# main_board.net
KiCad netlist of a schematic drawn in EAGLE
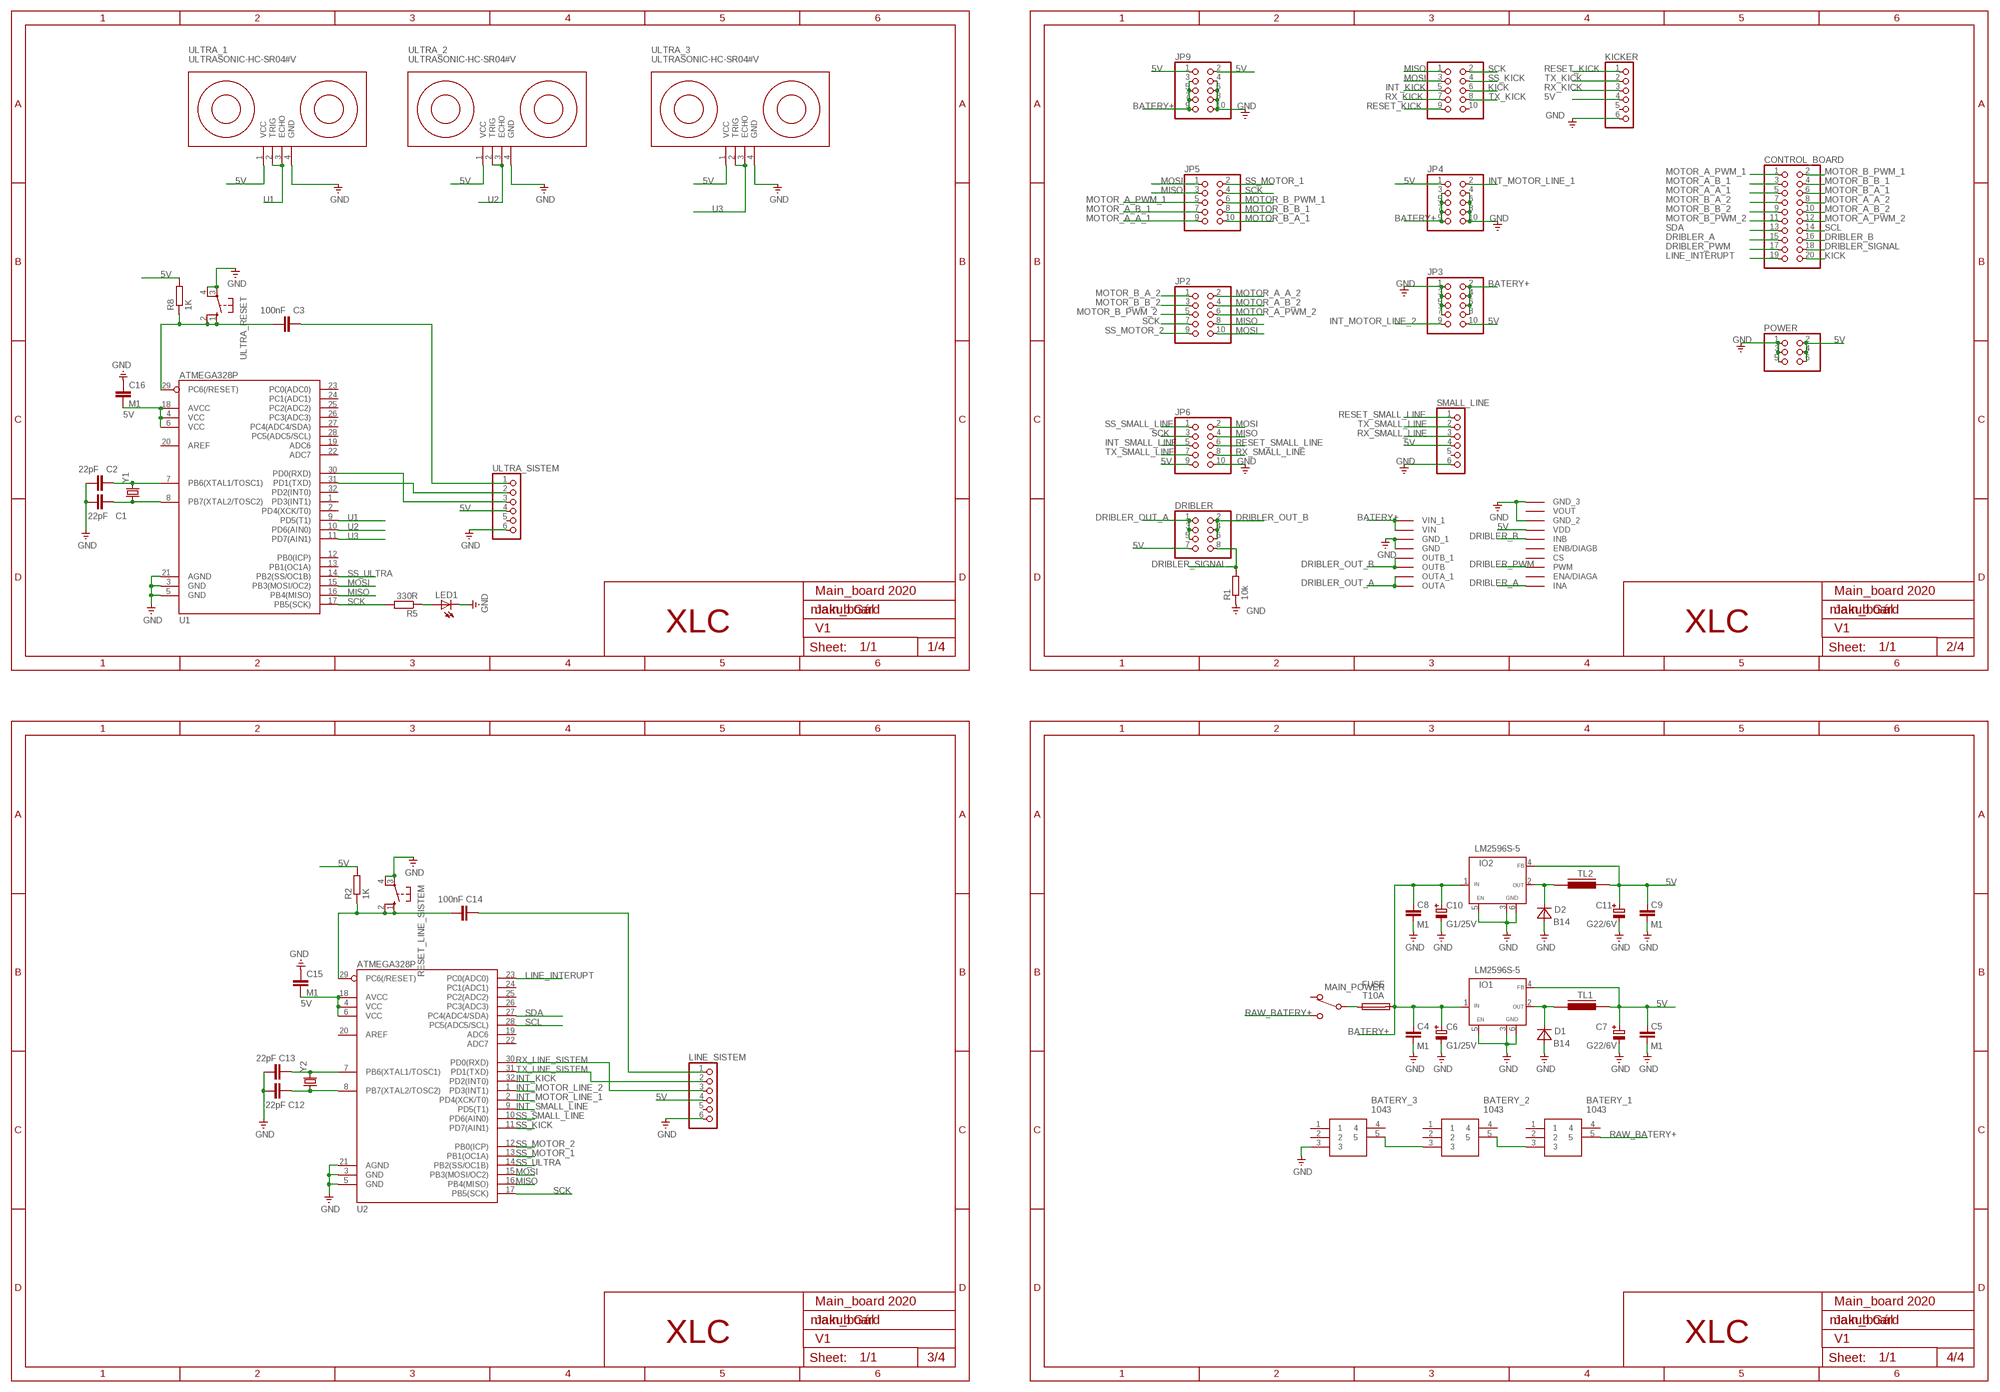
[diagram p0: schematic, sheet 1]

(export (version "E")
  (design (tool "Eeschema 10.0.6"))
  (components
    (comp (ref "BATERY_1")
      (value "1043")
      (footprint "eagle-import:1043")
      (fields (field (name "MOUSER_PART_NUMBER") "534-1043"))
      (libsource (lib "eagle-import") (part "1043"))
    )
    (comp (ref "BATERY_2")
      (value "1043")
      (footprint "eagle-import:1043")
      (fields (field (name "MOUSER_PART_NUMBER") "534-1043"))
      (libsource (lib "eagle-import") (part "1043"))
    )
    (comp (ref "BATERY_3")
      (value "1043")
      (footprint "eagle-import:1043")
      (fields (field (name "MOUSER_PART_NUMBER") "534-1043"))
      (libsource (lib "eagle-import") (part "1043"))
    )
    (comp (ref "C1")
      (value "22pF")
      (footprint "eagle-import:C0603")
      (libsource (lib "eagle-import") (part "C-EUC0603"))
    )
    (comp (ref "C2")
      (value "22pF")
      (footprint "eagle-import:C0603")
      (libsource (lib "eagle-import") (part "C-EUC0603"))
    )
    (comp (ref "C3")
      (value "100nF")
      (footprint "eagle-import:C0603")
      (libsource (lib "eagle-import") (part "C-EUC0603"))
    )
    (comp (ref "C4")
      (value "M1")
      (footprint "eagle-import:SMD-1206")
      (libsource (lib "eagle-import") (part "KOND-KERAM1206-SMD"))
    )
    (comp (ref "C5")
      (value "M1")
      (footprint "eagle-import:SMD-1206")
      (libsource (lib "eagle-import") (part "KOND-KERAM1206-SMD"))
    )
    (comp (ref "C6")
      (value "G1/25V")
      (footprint "eagle-import:SMD-ELE-D")
      (libsource (lib "eagle-import") (part "KOND-ELEKTD-SMD"))
    )
    (comp (ref "C7")
      (value "G22/6V")
      (footprint "eagle-import:SMD-ELE-D")
      (libsource (lib "eagle-import") (part "KOND-ELEKTD-SMD"))
    )
    (comp (ref "C8")
      (value "M1")
      (footprint "eagle-import:SMD-1206")
      (libsource (lib "eagle-import") (part "KOND-KERAM1206-SMD"))
    )
    (comp (ref "C9")
      (value "M1")
      (footprint "eagle-import:SMD-1206")
      (libsource (lib "eagle-import") (part "KOND-KERAM1206-SMD"))
    )
    (comp (ref "C10")
      (value "G1/25V")
      (footprint "eagle-import:SMD-ELE-D")
      (libsource (lib "eagle-import") (part "KOND-ELEKTD-SMD"))
    )
    (comp (ref "C11")
      (value "G22/6V")
      (footprint "eagle-import:SMD-ELE-D")
      (libsource (lib "eagle-import") (part "KOND-ELEKTD-SMD"))
    )
    (comp (ref "C12")
      (value "22pF")
      (footprint "eagle-import:C0603")
      (libsource (lib "eagle-import") (part "C-EUC0603"))
    )
    (comp (ref "C13")
      (value "22pF")
      (footprint "eagle-import:C0603")
      (libsource (lib "eagle-import") (part "C-EUC0603"))
    )
    (comp (ref "C14")
      (value "100nF")
      (footprint "eagle-import:C0603")
      (libsource (lib "eagle-import") (part "C-EUC0603"))
    )
    (comp (ref "C15")
      (value "M1")
      (footprint "eagle-import:C0603")
      (libsource (lib "eagle-import") (part "rcl_334_C-EUC0603"))
    )
    (comp (ref "C16")
      (value "M1")
      (footprint "eagle-import:C0603")
      (libsource (lib "eagle-import") (part "rcl_334_C-EUC0603"))
    )
    (comp (ref "CONTROL_BOARD")
      (value "PINHD-2X10_2.54-SMD")
      (footprint "eagle-import:2X10SMD")
      (libsource (lib "eagle-import") (part "PINHD-2X10_2.54-SMD"))
    )
    (comp (ref "D1")
      (value "B14")
      (footprint "eagle-import:D-3,6X5,5")
      (libsource (lib "eagle-import") (part "DIODASMD-3,6X5,5"))
    )
    (comp (ref "D2")
      (value "B14")
      (footprint "eagle-import:D-3,6X5,5")
      (libsource (lib "eagle-import") (part "DIODASMD-3,6X5,5"))
    )
    (comp (ref "DRIBLER")
      (value "PINHD-2X4_2.54-SMD")
      (footprint "eagle-import:2X04SMD")
      (libsource (lib "eagle-import") (part "PINHD-2X4_2.54-SMD"))
    )
    (comp (ref "FUSE")
      (value "T10A")
      (footprint "eagle-import:SH22,5A")
      (libsource (lib "eagle-import") (part "POISTKA2A"))
    )
    (comp (ref "IO1")
      (value "LM2596S-5")
      (footprint "eagle-import:TO263-5")
      (libsource (lib "eagle-import") (part "LM2596S"))
    )
    (comp (ref "IO2")
      (value "LM2596S-5")
      (footprint "eagle-import:TO263-5")
      (libsource (lib "eagle-import") (part "LM2596S"))
    )
    (comp (ref "JP2")
      (value "PINHD-2X5_2.54-SMD")
      (footprint "eagle-import:2X05SMD")
      (libsource (lib "eagle-import") (part "PINHD-2X5_2.54-SMD"))
    )
    (comp (ref "JP3")
      (value "PINHD-2X5_2.54-SMD")
      (footprint "eagle-import:2X05SMD")
      (libsource (lib "eagle-import") (part "PINHD-2X5_2.54-SMD"))
    )
    (comp (ref "JP4")
      (value "PINHD-2X5_2.54-SMD")
      (footprint "eagle-import:2X05SMD")
      (libsource (lib "eagle-import") (part "PINHD-2X5_2.54-SMD"))
    )
    (comp (ref "JP5")
      (value "PINHD-2X5_2.54-SMD")
      (footprint "eagle-import:2X05SMD")
      (libsource (lib "eagle-import") (part "PINHD-2X5_2.54-SMD"))
    )
    (comp (ref "JP6")
      (value "PINHD-2X5_2.54-SMD")
      (footprint "eagle-import:2X05SMD")
      (libsource (lib "eagle-import") (part "PINHD-2X5_2.54-SMD"))
    )
    (comp (ref "JP8")
      (value "PINHD-2X5_2.54-SMD")
      (footprint "eagle-import:2X05SMD")
      (libsource (lib "eagle-import") (part "PINHD-2X5_2.54-SMD"))
    )
    (comp (ref "JP9")
      (value "PINHD-2X5_2.54-SMD")
      (footprint "eagle-import:2X05SMD")
      (libsource (lib "eagle-import") (part "PINHD-2X5_2.54-SMD"))
    )
    (comp (ref "KICKER")
      (value "PINHD-1X6")
      (footprint "eagle-import:1X06")
      (libsource (lib "eagle-import") (part "PINHD-1X6"))
    )
    (comp (ref "LED1")
      (value "LEDCHIPLED_0603")
      (footprint "eagle-import:CHIPLED_0603")
      (libsource (lib "eagle-import") (part "LEDCHIPLED_0603"))
    )
    (comp (ref "LINE_SISTEM")
      (value "PINHD-1X6")
      (footprint "eagle-import:1X06")
      (libsource (lib "eagle-import") (part "PINHD-1X6"))
    )
    (comp (ref "MAIN_POWER")
      (value "PREP-1PB")
      (footprint "eagle-import:P-B069B")
      (libsource (lib "eagle-import") (part "PREP-1PB"))
    )
    (comp (ref "POWER")
      (value "PINHD-2X3_2.54-SMD")
      (footprint "eagle-import:2X03SMD")
      (libsource (lib "eagle-import") (part "PINHD-2X3_2.54-SMD"))
    )
    (comp (ref "R1")
      (value "10k")
      (footprint "eagle-import:R0603")
      (libsource (lib "eagle-import") (part "R-EU_R0603"))
    )
    (comp (ref "R2")
      (value "1K")
      (footprint "eagle-import:R0603")
      (libsource (lib "eagle-import") (part "R-EU_R0603"))
    )
    (comp (ref "R5")
      (value "330R")
      (footprint "eagle-import:R0603")
      (libsource (lib "eagle-import") (part "R-EU_R0603"))
    )
    (comp (ref "R8")
      (value "1K")
      (footprint "eagle-import:R0603")
      (libsource (lib "eagle-import") (part "R-EU_R0603"))
    )
    (comp (ref "RESET_LINE_SISTEM")
      (value "10-XX")
      (footprint "eagle-import:B3F-10XX")
      (fields (field (name "MPN") "B3F-1000"))
      (libsource (lib "eagle-import") (part "10-XX"))
    )
    (comp (ref "SMALL_LINE")
      (value "PINHD-1X6")
      (footprint "eagle-import:1X06")
      (libsource (lib "eagle-import") (part "PINHD-1X6"))
    )
    (comp (ref "TL1")
      (value "INDUK-TLSMD1")
      (footprint "eagle-import:INDUK-TL")
      (libsource (lib "eagle-import") (part "INDUK-TLSMD1"))
    )
    (comp (ref "TL2")
      (value "INDUK-TLSMD1")
      (footprint "eagle-import:INDUK-TL")
      (libsource (lib "eagle-import") (part "INDUK-TLSMD1"))
    )
    (comp (ref "U$4")
      (value "MOTOR_DRIVER")
      (footprint "eagle-import:MOTOR_DRIVER")
      (libsource (lib "eagle-import") (part "MOTOR_DRIVER"))
    )
    (comp (ref "U1")
      (value "ATMEGA328P")
      (footprint "eagle-import:TQFP32-08")
      (libsource (lib "eagle-import") (part "ATMEGA328_SMT"))
    )
    (comp (ref "U2")
      (value "ATMEGA328P")
      (footprint "eagle-import:TQFP32-08")
      (libsource (lib "eagle-import") (part "ATMEGA328_SMT"))
    )
    (comp (ref "ULTRA_1")
      (value "ULTRASONIC-HC-SR04#V")
      (footprint "eagle-import:ULTRASONIC-HC-SR04#V")
      (libsource (lib "eagle-import") (part "ULTRASONIC-HC-SR04#V"))
    )
    (comp (ref "ULTRA_2")
      (value "ULTRASONIC-HC-SR04#V")
      (footprint "eagle-import:ULTRASONIC-HC-SR04#V")
      (libsource (lib "eagle-import") (part "ULTRASONIC-HC-SR04#V"))
    )
    (comp (ref "ULTRA_3")
      (value "ULTRASONIC-HC-SR04#V")
      (footprint "eagle-import:ULTRASONIC-HC-SR04#V")
      (libsource (lib "eagle-import") (part "ULTRASONIC-HC-SR04#V"))
    )
    (comp (ref "ULTRA_RESET")
      (value "10-XX")
      (footprint "eagle-import:B3F-10XX")
      (fields (field (name "MPN") "B3F-1000"))
      (libsource (lib "eagle-import") (part "10-XX"))
    )
    (comp (ref "ULTRA_SISTEM")
      (value "PINHD-1X6")
      (footprint "eagle-import:1X06")
      (libsource (lib "eagle-import") (part "PINHD-1X6"))
    )
    (comp (ref "Y1")
      (value "CRYSTALHC49US")
      (footprint "eagle-import:HC49US")
      (libsource (lib "eagle-import") (part "CRYSTALHC49US"))
    )
    (comp (ref "Y2")
      (value "CRYSTALHC49US")
      (footprint "eagle-import:HC49US")
      (libsource (lib "eagle-import") (part "CRYSTALHC49US"))
    )
  )
  (nets
    (net (code "1") (name "/5V") (class "Default")
      (node (ref "C11") (pin "PLUS") (pinfunction "PLUS_PLUS") (pintype "passive"))
      (node (ref "C15") (pin "2") (pinfunction "2_2") (pintype "passive"))
      (node (ref "C16") (pin "2") (pinfunction "2_2") (pintype "passive"))
      (node (ref "C5") (pin "2") (pinfunction "2_2") (pintype "passive"))
      (node (ref "C7") (pin "PLUS") (pinfunction "PLUS_PLUS") (pintype "passive"))
      (node (ref "C9") (pin "2") (pinfunction "2_2") (pintype "passive"))
      (node (ref "DRIBLER") (pin "7") (pinfunction "7_7") (pintype "passive"))
      (node (ref "IO1") (pin "4") (pinfunction "FB_4") (pintype "input"))
      (node (ref "IO2") (pin "4") (pinfunction "FB_4") (pintype "input"))
      (node (ref "JP3") (pin "10") (pinfunction "10_10") (pintype "passive"))
      (node (ref "JP4") (pin "1") (pinfunction "1_1") (pintype "passive"))
      (node (ref "JP6") (pin "9") (pinfunction "9_9") (pintype "passive"))
      (node (ref "JP9") (pin "1") (pinfunction "1_1") (pintype "passive"))
      (node (ref "JP9") (pin "2") (pinfunction "2_2") (pintype "passive"))
      (node (ref "KICKER") (pin "4") (pinfunction "4_4") (pintype "passive"))
      (node (ref "LINE_SISTEM") (pin "4") (pinfunction "4_4") (pintype "passive"))
      (node (ref "POWER") (pin "2") (pinfunction "2_2") (pintype "passive"))
      (node (ref "POWER") (pin "4") (pinfunction "4_4") (pintype "passive"))
      (node (ref "POWER") (pin "6") (pinfunction "6_6") (pintype "passive"))
      (node (ref "R2") (pin "2") (pinfunction "2_2") (pintype "passive"))
      (node (ref "R8") (pin "2") (pinfunction "2_2") (pintype "passive"))
      (node (ref "SMALL_LINE") (pin "4") (pinfunction "4_4") (pintype "passive"))
      (node (ref "TL1") (pin "2") (pinfunction "2_2") (pintype "passive"))
      (node (ref "TL2") (pin "2") (pinfunction "2_2") (pintype "passive"))
      (node (ref "U$4") (pin "VDD") (pinfunction "VDD_VDD") (pintype "bidirectional"))
      (node (ref "U1") (pin "18") (pinfunction "AVCC_18") (pintype "bidirectional"))
      (node (ref "U1") (pin "4") (pinfunction "VCC_4") (pintype "bidirectional"))
      (node (ref "U1") (pin "6") (pinfunction "VCC_6") (pintype "bidirectional"))
      (node (ref "U2") (pin "18") (pinfunction "AVCC_18") (pintype "bidirectional"))
      (node (ref "U2") (pin "4") (pinfunction "VCC_4") (pintype "bidirectional"))
      (node (ref "U2") (pin "6") (pinfunction "VCC_6") (pintype "bidirectional"))
      (node (ref "ULTRA_1") (pin "1") (pinfunction "VCC_1") (pintype "power_in"))
      (node (ref "ULTRA_2") (pin "1") (pinfunction "VCC_1") (pintype "power_in"))
      (node (ref "ULTRA_3") (pin "1") (pinfunction "VCC_1") (pintype "power_in"))
      (node (ref "ULTRA_SISTEM") (pin "4") (pinfunction "4_4") (pintype "passive"))
    )
    (net (code "2") (name "/BATERY+") (class "Default")
      (node (ref "C10") (pin "PLUS") (pinfunction "PLUS_PLUS") (pintype "passive"))
      (node (ref "C4") (pin "2") (pinfunction "2_2") (pintype "passive"))
      (node (ref "C6") (pin "PLUS") (pinfunction "PLUS_PLUS") (pintype "passive"))
      (node (ref "C8") (pin "2") (pinfunction "2_2") (pintype "passive"))
      (node (ref "FUSE") (pin "2") (pinfunction "2_2") (pintype "passive"))
      (node (ref "IO1") (pin "1") (pinfunction "IN_1") (pintype "input"))
      (node (ref "IO2") (pin "1") (pinfunction "IN_1") (pintype "input"))
      (node (ref "JP3") (pin "2") (pinfunction "2_2") (pintype "passive"))
      (node (ref "JP3") (pin "4") (pinfunction "4_4") (pintype "passive"))
      (node (ref "JP3") (pin "6") (pinfunction "6_6") (pintype "passive"))
      (node (ref "JP3") (pin "8") (pinfunction "8_8") (pintype "passive"))
      (node (ref "JP4") (pin "3") (pinfunction "3_3") (pintype "passive"))
      (node (ref "JP4") (pin "5") (pinfunction "5_5") (pintype "passive"))
      (node (ref "JP4") (pin "7") (pinfunction "7_7") (pintype "passive"))
      (node (ref "JP4") (pin "9") (pinfunction "9_9") (pintype "passive"))
      (node (ref "JP9") (pin "3") (pinfunction "3_3") (pintype "passive"))
      (node (ref "JP9") (pin "5") (pinfunction "5_5") (pintype "passive"))
      (node (ref "JP9") (pin "7") (pinfunction "7_7") (pintype "passive"))
      (node (ref "JP9") (pin "9") (pinfunction "9_9") (pintype "passive"))
      (node (ref "U$4") (pin "VIN") (pinfunction "VIN_VIN") (pintype "bidirectional"))
      (node (ref "U$4") (pin "VIN_1") (pinfunction "VIN_1_VIN_1") (pintype "bidirectional"))
    )
    (net (code "3") (name "/DRIBLER_A") (class "Default")
      (node (ref "CONTROL_BOARD") (pin "15") (pinfunction "15_15") (pintype "passive"))
      (node (ref "U$4") (pin "INA") (pinfunction "INA_INA") (pintype "bidirectional"))
    )
    (net (code "4") (name "/DRIBLER_B") (class "Default")
      (node (ref "CONTROL_BOARD") (pin "16") (pinfunction "16_16") (pintype "passive"))
      (node (ref "U$4") (pin "INB") (pinfunction "INB_INB") (pintype "bidirectional"))
    )
    (net (code "5") (name "/DRIBLER_OUT_A") (class "Default")
      (node (ref "DRIBLER") (pin "1") (pinfunction "1_1") (pintype "passive"))
      (node (ref "DRIBLER") (pin "3") (pinfunction "3_3") (pintype "passive"))
      (node (ref "DRIBLER") (pin "5") (pinfunction "5_5") (pintype "passive"))
      (node (ref "U$4") (pin "OUTA") (pinfunction "OUTA_OUTA") (pintype "bidirectional"))
      (node (ref "U$4") (pin "OUTA_1") (pinfunction "OUTA_1_OUTA_1") (pintype "bidirectional"))
    )
    (net (code "6") (name "/DRIBLER_OUT_B") (class "Default")
      (node (ref "DRIBLER") (pin "2") (pinfunction "2_2") (pintype "passive"))
      (node (ref "DRIBLER") (pin "4") (pinfunction "4_4") (pintype "passive"))
      (node (ref "DRIBLER") (pin "6") (pinfunction "6_6") (pintype "passive"))
      (node (ref "U$4") (pin "OUTB") (pinfunction "OUTB_OUTB") (pintype "bidirectional"))
      (node (ref "U$4") (pin "OUTB_1") (pinfunction "OUTB_1_OUTB_1") (pintype "bidirectional"))
    )
    (net (code "7") (name "/DRIBLER_PWM") (class "Default")
      (node (ref "CONTROL_BOARD") (pin "17") (pinfunction "17_17") (pintype "passive"))
      (node (ref "U$4") (pin "PWM") (pinfunction "PWM_PWM") (pintype "bidirectional"))
    )
    (net (code "8") (name "/DRIBLER_SIGNAL") (class "Default")
      (node (ref "CONTROL_BOARD") (pin "18") (pinfunction "18_18") (pintype "passive"))
      (node (ref "DRIBLER") (pin "8") (pinfunction "8_8") (pintype "passive"))
      (node (ref "R1") (pin "2") (pinfunction "2_2") (pintype "passive"))
    )
    (net (code "9") (name "/INT_KICK") (class "Default")
      (node (ref "JP8") (pin "5") (pinfunction "5_5") (pintype "passive"))
      (node (ref "U2") (pin "32") (pinfunction "PD2(INT0)_32") (pintype "bidirectional"))
    )
    (net (code "10") (name "/INT_MOTOR_LINE_1") (class "Default")
      (node (ref "JP4") (pin "2") (pinfunction "2_2") (pintype "passive"))
      (node (ref "U2") (pin "2") (pinfunction "PD4(XCK/T0)_2") (pintype "bidirectional"))
    )
    (net (code "11") (name "/INT_MOTOR_LINE_2") (class "Default")
      (node (ref "JP3") (pin "9") (pinfunction "9_9") (pintype "passive"))
      (node (ref "U2") (pin "1") (pinfunction "PD3(INT1)_1") (pintype "bidirectional"))
    )
    (net (code "12") (name "/INT_SMALL_LINE") (class "Default")
      (node (ref "JP6") (pin "5") (pinfunction "5_5") (pintype "passive"))
      (node (ref "U2") (pin "9") (pinfunction "PD5(T1)_9") (pintype "bidirectional"))
    )
    (net (code "13") (name "/KICK") (class "Default")
      (node (ref "CONTROL_BOARD") (pin "20") (pinfunction "20_20") (pintype "passive"))
      (node (ref "JP8") (pin "6") (pinfunction "6_6") (pintype "passive"))
    )
    (net (code "14") (name "/LINE_INTERUPT") (class "Default")
      (node (ref "CONTROL_BOARD") (pin "19") (pinfunction "19_19") (pintype "passive"))
      (node (ref "U2") (pin "23") (pinfunction "PC0(ADC0)_23") (pintype "bidirectional"))
    )
    (net (code "15") (name "/MISO") (class "Default")
      (node (ref "JP2") (pin "8") (pinfunction "8_8") (pintype "passive"))
      (node (ref "JP5") (pin "3") (pinfunction "3_3") (pintype "passive"))
      (node (ref "JP6") (pin "4") (pinfunction "4_4") (pintype "passive"))
      (node (ref "JP8") (pin "1") (pinfunction "1_1") (pintype "passive"))
      (node (ref "U1") (pin "16") (pinfunction "PB4(MISO)_16") (pintype "bidirectional"))
      (node (ref "U2") (pin "16") (pinfunction "PB4(MISO)_16") (pintype "bidirectional"))
    )
    (net (code "16") (name "/MOSI") (class "Default")
      (node (ref "JP2") (pin "10") (pinfunction "10_10") (pintype "passive"))
      (node (ref "JP5") (pin "1") (pinfunction "1_1") (pintype "passive"))
      (node (ref "JP6") (pin "2") (pinfunction "2_2") (pintype "passive"))
      (node (ref "JP8") (pin "3") (pinfunction "3_3") (pintype "passive"))
      (node (ref "U1") (pin "15") (pinfunction "PB3(MOSI/OC2)_15") (pintype "bidirectional"))
      (node (ref "U2") (pin "15") (pinfunction "PB3(MOSI/OC2)_15") (pintype "bidirectional"))
    )
    (net (code "17") (name "/MOTOR_A_A_1") (class "Default")
      (node (ref "CONTROL_BOARD") (pin "5") (pinfunction "5_5") (pintype "passive"))
      (node (ref "JP5") (pin "9") (pinfunction "9_9") (pintype "passive"))
    )
    (net (code "18") (name "/MOTOR_A_A_2") (class "Default")
      (node (ref "CONTROL_BOARD") (pin "8") (pinfunction "8_8") (pintype "passive"))
      (node (ref "JP2") (pin "2") (pinfunction "2_2") (pintype "passive"))
    )
    (net (code "19") (name "/MOTOR_A_B_1") (class "Default")
      (node (ref "CONTROL_BOARD") (pin "3") (pinfunction "3_3") (pintype "passive"))
      (node (ref "JP5") (pin "7") (pinfunction "7_7") (pintype "passive"))
    )
    (net (code "20") (name "/MOTOR_A_B_2") (class "Default")
      (node (ref "CONTROL_BOARD") (pin "10") (pinfunction "10_10") (pintype "passive"))
      (node (ref "JP2") (pin "4") (pinfunction "4_4") (pintype "passive"))
    )
    (net (code "21") (name "/MOTOR_A_PWM_1") (class "Default")
      (node (ref "CONTROL_BOARD") (pin "1") (pinfunction "1_1") (pintype "passive"))
      (node (ref "JP5") (pin "5") (pinfunction "5_5") (pintype "passive"))
    )
    (net (code "22") (name "/MOTOR_A_PWM_2") (class "Default")
      (node (ref "CONTROL_BOARD") (pin "12") (pinfunction "12_12") (pintype "passive"))
      (node (ref "JP2") (pin "6") (pinfunction "6_6") (pintype "passive"))
    )
    (net (code "23") (name "/MOTOR_B_A_1") (class "Default")
      (node (ref "CONTROL_BOARD") (pin "6") (pinfunction "6_6") (pintype "passive"))
      (node (ref "JP5") (pin "10") (pinfunction "10_10") (pintype "passive"))
    )
    (net (code "24") (name "/MOTOR_B_A_2") (class "Default")
      (node (ref "CONTROL_BOARD") (pin "7") (pinfunction "7_7") (pintype "passive"))
      (node (ref "JP2") (pin "1") (pinfunction "1_1") (pintype "passive"))
    )
    (net (code "25") (name "/MOTOR_B_B_1") (class "Default")
      (node (ref "CONTROL_BOARD") (pin "4") (pinfunction "4_4") (pintype "passive"))
      (node (ref "JP5") (pin "8") (pinfunction "8_8") (pintype "passive"))
    )
    (net (code "26") (name "/MOTOR_B_B_2") (class "Default")
      (node (ref "CONTROL_BOARD") (pin "9") (pinfunction "9_9") (pintype "passive"))
      (node (ref "JP2") (pin "3") (pinfunction "3_3") (pintype "passive"))
    )
    (net (code "27") (name "/MOTOR_B_PWM_1") (class "Default")
      (node (ref "CONTROL_BOARD") (pin "2") (pinfunction "2_2") (pintype "passive"))
      (node (ref "JP5") (pin "6") (pinfunction "6_6") (pintype "passive"))
    )
    (net (code "28") (name "/MOTOR_B_PWM_2") (class "Default")
      (node (ref "CONTROL_BOARD") (pin "11") (pinfunction "11_11") (pintype "passive"))
      (node (ref "JP2") (pin "5") (pinfunction "5_5") (pintype "passive"))
    )
    (net (code "29") (name "/RAW_BATERY+") (class "Default")
      (node (ref "BATERY_1") (pin "5") (pinfunction "5_5") (pintype "bidirectional"))
      (node (ref "MAIN_POWER") (pin "1") (pinfunction "1-OFF_1") (pintype "passive"))
    )
    (net (code "30") (name "/RESET_KICK") (class "Default")
      (node (ref "JP8") (pin "9") (pinfunction "9_9") (pintype "passive"))
      (node (ref "KICKER") (pin "1") (pinfunction "1_1") (pintype "passive"))
    )
    (net (code "31") (name "/RESET_SMALL_LINE") (class "Default")
      (node (ref "JP6") (pin "6") (pinfunction "6_6") (pintype "passive"))
      (node (ref "SMALL_LINE") (pin "1") (pinfunction "1_1") (pintype "passive"))
    )
    (net (code "32") (name "/RX_KICK") (class "Default")
      (node (ref "JP8") (pin "7") (pinfunction "7_7") (pintype "passive"))
      (node (ref "KICKER") (pin "3") (pinfunction "3_3") (pintype "passive"))
    )
    (net (code "33") (name "/RX_LINE_SISTEM") (class "Default")
      (node (ref "LINE_SISTEM") (pin "3") (pinfunction "3_3") (pintype "passive"))
      (node (ref "U2") (pin "30") (pinfunction "PD0(RXD)_30") (pintype "bidirectional"))
    )
    (net (code "34") (name "/RX_SMALL_LINE") (class "Default")
      (node (ref "JP6") (pin "8") (pinfunction "8_8") (pintype "passive"))
      (node (ref "SMALL_LINE") (pin "3") (pinfunction "3_3") (pintype "passive"))
    )
    (net (code "35") (name "/SCK") (class "Default")
      (node (ref "JP2") (pin "7") (pinfunction "7_7") (pintype "passive"))
      (node (ref "JP5") (pin "4") (pinfunction "4_4") (pintype "passive"))
      (node (ref "JP6") (pin "3") (pinfunction "3_3") (pintype "passive"))
      (node (ref "JP8") (pin "2") (pinfunction "2_2") (pintype "passive"))
      (node (ref "R5") (pin "2") (pinfunction "2_2") (pintype "passive"))
      (node (ref "U1") (pin "17") (pinfunction "PB5(SCK)_17") (pintype "bidirectional"))
      (node (ref "U2") (pin "17") (pinfunction "PB5(SCK)_17") (pintype "bidirectional"))
    )
    (net (code "36") (name "/SCL") (class "Default")
      (node (ref "CONTROL_BOARD") (pin "14") (pinfunction "14_14") (pintype "passive"))
      (node (ref "U2") (pin "28") (pinfunction "PC5(ADC5/SCL)_28") (pintype "bidirectional"))
    )
    (net (code "37") (name "/SDA") (class "Default")
      (node (ref "CONTROL_BOARD") (pin "13") (pinfunction "13_13") (pintype "passive"))
      (node (ref "U2") (pin "27") (pinfunction "PC4(ADC4/SDA)_27") (pintype "bidirectional"))
    )
    (net (code "38") (name "/SS_KICK") (class "Default")
      (node (ref "JP8") (pin "4") (pinfunction "4_4") (pintype "passive"))
      (node (ref "U2") (pin "11") (pinfunction "PD7(AIN1)_11") (pintype "bidirectional"))
    )
    (net (code "39") (name "/SS_MOTOR_1") (class "Default")
      (node (ref "JP5") (pin "2") (pinfunction "2_2") (pintype "passive"))
      (node (ref "U2") (pin "13") (pinfunction "PB1(OC1A)_13") (pintype "bidirectional"))
    )
    (net (code "40") (name "/SS_MOTOR_2") (class "Default")
      (node (ref "JP2") (pin "9") (pinfunction "9_9") (pintype "passive"))
      (node (ref "U2") (pin "12") (pinfunction "PB0(ICP)_12") (pintype "bidirectional"))
    )
    (net (code "41") (name "/SS_SMALL_LINE") (class "Default")
      (node (ref "JP6") (pin "1") (pinfunction "1_1") (pintype "passive"))
      (node (ref "U2") (pin "10") (pinfunction "PD6(AIN0)_10") (pintype "bidirectional"))
    )
    (net (code "42") (name "/SS_ULTRA") (class "Default")
      (node (ref "U1") (pin "14") (pinfunction "PB2(SS/OC1B)_14") (pintype "bidirectional"))
      (node (ref "U2") (pin "14") (pinfunction "PB2(SS/OC1B)_14") (pintype "bidirectional"))
    )
    (net (code "43") (name "/TX_KICK") (class "Default")
      (node (ref "JP8") (pin "8") (pinfunction "8_8") (pintype "passive"))
      (node (ref "KICKER") (pin "2") (pinfunction "2_2") (pintype "passive"))
    )
    (net (code "44") (name "/TX_LINE_SISTEM") (class "Default")
      (node (ref "LINE_SISTEM") (pin "2") (pinfunction "2_2") (pintype "passive"))
      (node (ref "U2") (pin "31") (pinfunction "PD1(TXD)_31") (pintype "bidirectional"))
    )
    (net (code "45") (name "/TX_SMALL_LINE") (class "Default")
      (node (ref "JP6") (pin "7") (pinfunction "7_7") (pintype "passive"))
      (node (ref "SMALL_LINE") (pin "2") (pinfunction "2_2") (pintype "passive"))
    )
    (net (code "46") (name "/U1") (class "Default")
      (node (ref "U1") (pin "9") (pinfunction "PD5(T1)_9") (pintype "bidirectional"))
      (node (ref "ULTRA_1") (pin "2") (pinfunction "TRIG_2") (pintype "input"))
      (node (ref "ULTRA_1") (pin "3") (pinfunction "ECHO_3") (pintype "output"))
    )
    (net (code "47") (name "/U2") (class "Default")
      (node (ref "U1") (pin "10") (pinfunction "PD6(AIN0)_10") (pintype "bidirectional"))
      (node (ref "ULTRA_2") (pin "2") (pinfunction "TRIG_2") (pintype "input"))
      (node (ref "ULTRA_2") (pin "3") (pinfunction "ECHO_3") (pintype "output"))
    )
    (net (code "48") (name "/U3") (class "Default")
      (node (ref "U1") (pin "11") (pinfunction "PD7(AIN1)_11") (pintype "bidirectional"))
      (node (ref "ULTRA_3") (pin "2") (pinfunction "TRIG_2") (pintype "input"))
      (node (ref "ULTRA_3") (pin "3") (pinfunction "ECHO_3") (pintype "output"))
    )
    (net (code "49") (name "GND") (class "Default")
      (node (ref "BATERY_3") (pin "3") (pinfunction "3_3") (pintype "bidirectional"))
      (node (ref "C1") (pin "1") (pinfunction "1_1") (pintype "passive"))
      (node (ref "C10") (pin "MINUS") (pinfunction "MINUS_MINUS") (pintype "passive"))
      (node (ref "C11") (pin "MINUS") (pinfunction "MINUS_MINUS") (pintype "passive"))
      (node (ref "C12") (pin "1") (pinfunction "1_1") (pintype "passive"))
      (node (ref "C13") (pin "1") (pinfunction "1_1") (pintype "passive"))
      (node (ref "C15") (pin "1") (pinfunction "1_1") (pintype "passive"))
      (node (ref "C16") (pin "1") (pinfunction "1_1") (pintype "passive"))
      (node (ref "C2") (pin "1") (pinfunction "1_1") (pintype "passive"))
      (node (ref "C4") (pin "1") (pinfunction "1_1") (pintype "passive"))
      (node (ref "C5") (pin "1") (pinfunction "1_1") (pintype "passive"))
      (node (ref "C6") (pin "MINUS") (pinfunction "MINUS_MINUS") (pintype "passive"))
      (node (ref "C7") (pin "MINUS") (pinfunction "MINUS_MINUS") (pintype "passive"))
      (node (ref "C8") (pin "1") (pinfunction "1_1") (pintype "passive"))
      (node (ref "C9") (pin "1") (pinfunction "1_1") (pintype "passive"))
      (node (ref "D1") (pin "A") (pinfunction "A_A") (pintype "passive"))
      (node (ref "D2") (pin "A") (pinfunction "A_A") (pintype "passive"))
      (node (ref "IO1") (pin "3") (pinfunction "GND_3") (pintype "power_in"))
      (node (ref "IO1") (pin "5") (pinfunction "EN_5") (pintype "input"))
      (node (ref "IO1") (pin "6") (pinfunction "GND_6") (pintype "power_in"))
      (node (ref "IO2") (pin "3") (pinfunction "GND_3") (pintype "power_in"))
      (node (ref "IO2") (pin "5") (pinfunction "EN_5") (pintype "input"))
      (node (ref "IO2") (pin "6") (pinfunction "GND_6") (pintype "power_in"))
      (node (ref "JP3") (pin "1") (pinfunction "1_1") (pintype "passive"))
      (node (ref "JP3") (pin "3") (pinfunction "3_3") (pintype "passive"))
      (node (ref "JP3") (pin "5") (pinfunction "5_5") (pintype "passive"))
      (node (ref "JP3") (pin "7") (pinfunction "7_7") (pintype "passive"))
      (node (ref "JP4") (pin "10") (pinfunction "10_10") (pintype "passive"))
      (node (ref "JP4") (pin "4") (pinfunction "4_4") (pintype "passive"))
      (node (ref "JP4") (pin "6") (pinfunction "6_6") (pintype "passive"))
      (node (ref "JP4") (pin "8") (pinfunction "8_8") (pintype "passive"))
      (node (ref "JP6") (pin "10") (pinfunction "10_10") (pintype "passive"))
      (node (ref "JP9") (pin "10") (pinfunction "10_10") (pintype "passive"))
      (node (ref "JP9") (pin "4") (pinfunction "4_4") (pintype "passive"))
      (node (ref "JP9") (pin "6") (pinfunction "6_6") (pintype "passive"))
      (node (ref "JP9") (pin "8") (pinfunction "8_8") (pintype "passive"))
      (node (ref "KICKER") (pin "6") (pinfunction "6_6") (pintype "passive"))
      (node (ref "LED1") (pin "C") (pinfunction "C_C") (pintype "passive"))
      (node (ref "LINE_SISTEM") (pin "6") (pinfunction "6_6") (pintype "passive"))
      (node (ref "POWER") (pin "1") (pinfunction "1_1") (pintype "passive"))
      (node (ref "POWER") (pin "3") (pinfunction "3_3") (pintype "passive"))
      (node (ref "POWER") (pin "5") (pinfunction "5_5") (pintype "passive"))
      (node (ref "R1") (pin "1") (pinfunction "1_1") (pintype "passive"))
      (node (ref "RESET_LINE_SISTEM") (pin "3") (pinfunction "P_3") (pintype "passive"))
      (node (ref "RESET_LINE_SISTEM") (pin "4") (pinfunction "P1_4") (pintype "passive"))
      (node (ref "SMALL_LINE") (pin "6") (pinfunction "6_6") (pintype "passive"))
      (node (ref "U$4") (pin "GND") (pinfunction "GND_GND") (pintype "bidirectional"))
      (node (ref "U$4") (pin "GND_1") (pinfunction "GND_1_GND_1") (pintype "bidirectional"))
      (node (ref "U$4") (pin "GND_2") (pinfunction "GND_2_GND_2") (pintype "bidirectional"))
      (node (ref "U$4") (pin "GND_3") (pinfunction "GND_3_GND_3") (pintype "bidirectional"))
      (node (ref "U1") (pin "21") (pinfunction "AGND_21") (pintype "bidirectional"))
      (node (ref "U1") (pin "3") (pinfunction "GND_3") (pintype "bidirectional"))
      (node (ref "U1") (pin "5") (pinfunction "GND_5") (pintype "bidirectional"))
      (node (ref "U2") (pin "21") (pinfunction "AGND_21") (pintype "bidirectional"))
      (node (ref "U2") (pin "3") (pinfunction "GND_3") (pintype "bidirectional"))
      (node (ref "U2") (pin "5") (pinfunction "GND_5") (pintype "bidirectional"))
      (node (ref "ULTRA_1") (pin "4") (pinfunction "GND_4") (pintype "power_in"))
      (node (ref "ULTRA_2") (pin "4") (pinfunction "GND_4") (pintype "power_in"))
      (node (ref "ULTRA_3") (pin "4") (pinfunction "GND_4") (pintype "power_in"))
      (node (ref "ULTRA_RESET") (pin "3") (pinfunction "P_3") (pintype "passive"))
      (node (ref "ULTRA_RESET") (pin "4") (pinfunction "P1_4") (pintype "passive"))
      (node (ref "ULTRA_SISTEM") (pin "6") (pinfunction "6_6") (pintype "passive"))
    )
    (net (code "50") (name "Net-(BATERY_1-Pad3)") (class "Default")
      (node (ref "BATERY_1") (pin "3") (pinfunction "3_3") (pintype "bidirectional"))
      (node (ref "BATERY_2") (pin "5") (pinfunction "5_5") (pintype "bidirectional"))
    )
    (net (code "51") (name "Net-(BATERY_2-Pad3)") (class "Default")
      (node (ref "BATERY_2") (pin "3") (pinfunction "3_3") (pintype "bidirectional"))
      (node (ref "BATERY_3") (pin "5") (pinfunction "5_5") (pintype "bidirectional"))
    )
    (net (code "52") (name "Net-(C3-Pad2)") (class "Default")
      (node (ref "C3") (pin "2") (pinfunction "2_2") (pintype "passive"))
      (node (ref "ULTRA_SISTEM") (pin "1") (pinfunction "1_1") (pintype "passive"))
    )
    (net (code "53") (name "Net-(C14-Pad2)") (class "Default")
      (node (ref "C14") (pin "2") (pinfunction "2_2") (pintype "passive"))
      (node (ref "LINE_SISTEM") (pin "1") (pinfunction "1_1") (pintype "passive"))
    )
    (net (code "54") (name "Net-(IO1-OUT)") (class "Default")
      (node (ref "D1") (pin "K") (pinfunction "K_K") (pintype "passive"))
      (node (ref "IO1") (pin "2") (pinfunction "OUT_2") (pintype "output"))
      (node (ref "TL1") (pin "1") (pinfunction "1_1") (pintype "passive"))
    )
    (net (code "55") (name "Net-(IO2-OUT)") (class "Default")
      (node (ref "D2") (pin "K") (pinfunction "K_K") (pintype "passive"))
      (node (ref "IO2") (pin "2") (pinfunction "OUT_2") (pintype "output"))
      (node (ref "TL2") (pin "1") (pinfunction "1_1") (pintype "passive"))
    )
    (net (code "56") (name "Net-(LED1-PadA)") (class "Default")
      (node (ref "LED1") (pin "A") (pinfunction "A_A") (pintype "passive"))
      (node (ref "R5") (pin "1") (pinfunction "1_1") (pintype "passive"))
    )
    (net (code "57") (name "Net-(MAIN_POWER-2-COM)") (class "Default")
      (node (ref "FUSE") (pin "1") (pinfunction "1_1") (pintype "passive"))
      (node (ref "MAIN_POWER") (pin "2") (pinfunction "2-COM_2") (pintype "passive"))
    )
    (net (code "58") (name "Net-(RESET_LINE_SISTEM-S)") (class "Default")
      (node (ref "C14") (pin "1") (pinfunction "1_1") (pintype "passive"))
      (node (ref "R2") (pin "1") (pinfunction "1_1") (pintype "passive"))
      (node (ref "RESET_LINE_SISTEM") (pin "1") (pinfunction "S_1") (pintype "passive"))
      (node (ref "RESET_LINE_SISTEM") (pin "2") (pinfunction "S1_2") (pintype "passive"))
      (node (ref "U2") (pin "29") (pinfunction "PC6(/RESET)_29") (pintype "bidirectional"))
    )
    (net (code "59") (name "Net-(U1-PB6(XTAL1{slash}TOSC1))") (class "Default")
      (node (ref "C2") (pin "2") (pinfunction "2_2") (pintype "passive"))
      (node (ref "U1") (pin "7") (pinfunction "PB6(XTAL1/TOSC1)_7") (pintype "bidirectional"))
      (node (ref "Y1") (pin "2") (pinfunction "2_2") (pintype "passive"))
    )
    (net (code "60") (name "Net-(U1-PB7(XTAL2{slash}TOSC2))") (class "Default")
      (node (ref "C1") (pin "2") (pinfunction "2_2") (pintype "passive"))
      (node (ref "U1") (pin "8") (pinfunction "PB7(XTAL2/TOSC2)_8") (pintype "bidirectional"))
      (node (ref "Y1") (pin "1") (pinfunction "1_1") (pintype "passive"))
    )
    (net (code "61") (name "Net-(U1-PC6({slash}RESET))") (class "Default")
      (node (ref "C3") (pin "1") (pinfunction "1_1") (pintype "passive"))
      (node (ref "R8") (pin "1") (pinfunction "1_1") (pintype "passive"))
      (node (ref "U1") (pin "29") (pinfunction "PC6(/RESET)_29") (pintype "bidirectional"))
      (node (ref "ULTRA_RESET") (pin "1") (pinfunction "S_1") (pintype "passive"))
      (node (ref "ULTRA_RESET") (pin "2") (pinfunction "S1_2") (pintype "passive"))
    )
    (net (code "62") (name "Net-(U1-PD0(RXD))") (class "Default")
      (node (ref "U1") (pin "30") (pinfunction "PD0(RXD)_30") (pintype "bidirectional"))
      (node (ref "ULTRA_SISTEM") (pin "3") (pinfunction "3_3") (pintype "passive"))
    )
    (net (code "63") (name "Net-(U1-PD1(TXD))") (class "Default")
      (node (ref "U1") (pin "31") (pinfunction "PD1(TXD)_31") (pintype "bidirectional"))
      (node (ref "ULTRA_SISTEM") (pin "2") (pinfunction "2_2") (pintype "passive"))
    )
    (net (code "64") (name "Net-(U2-PB6(XTAL1{slash}TOSC1))") (class "Default")
      (node (ref "C13") (pin "2") (pinfunction "2_2") (pintype "passive"))
      (node (ref "U2") (pin "7") (pinfunction "PB6(XTAL1/TOSC1)_7") (pintype "bidirectional"))
      (node (ref "Y2") (pin "2") (pinfunction "2_2") (pintype "passive"))
    )
    (net (code "65") (name "Net-(U2-PB7(XTAL2{slash}TOSC2))") (class "Default")
      (node (ref "C12") (pin "2") (pinfunction "2_2") (pintype "passive"))
      (node (ref "U2") (pin "8") (pinfunction "PB7(XTAL2/TOSC2)_8") (pintype "bidirectional"))
      (node (ref "Y2") (pin "1") (pinfunction "1_1") (pintype "passive"))
    )
    (net (code "66") (name "unconnected-(BATERY_1-Pad1)") (class "Default")
      (node (ref "BATERY_1") (pin "1") (pinfunction "1_1") (pintype "bidirectional"))
    )
    (net (code "67") (name "unconnected-(BATERY_1-Pad2)") (class "Default")
      (node (ref "BATERY_1") (pin "2") (pinfunction "2_2") (pintype "bidirectional"))
    )
    (net (code "68") (name "unconnected-(BATERY_1-Pad4)") (class "Default")
      (node (ref "BATERY_1") (pin "4") (pinfunction "4_4") (pintype "bidirectional"))
    )
    (net (code "69") (name "unconnected-(BATERY_2-Pad1)") (class "Default")
      (node (ref "BATERY_2") (pin "1") (pinfunction "1_1") (pintype "bidirectional"))
    )
    (net (code "70") (name "unconnected-(BATERY_2-Pad2)") (class "Default")
      (node (ref "BATERY_2") (pin "2") (pinfunction "2_2") (pintype "bidirectional"))
    )
    (net (code "71") (name "unconnected-(BATERY_2-Pad4)") (class "Default")
      (node (ref "BATERY_2") (pin "4") (pinfunction "4_4") (pintype "bidirectional"))
    )
    (net (code "72") (name "unconnected-(BATERY_3-Pad1)") (class "Default")
      (node (ref "BATERY_3") (pin "1") (pinfunction "1_1") (pintype "bidirectional"))
    )
    (net (code "73") (name "unconnected-(BATERY_3-Pad2)") (class "Default")
      (node (ref "BATERY_3") (pin "2") (pinfunction "2_2") (pintype "bidirectional"))
    )
    (net (code "74") (name "unconnected-(BATERY_3-Pad4)") (class "Default")
      (node (ref "BATERY_3") (pin "4") (pinfunction "4_4") (pintype "bidirectional"))
    )
    (net (code "75") (name "unconnected-(JP8-Pad10)") (class "Default")
      (node (ref "JP8") (pin "10") (pinfunction "10_10") (pintype "passive"))
    )
    (net (code "76") (name "unconnected-(KICKER-Pad5)") (class "Default")
      (node (ref "KICKER") (pin "5") (pinfunction "5_5") (pintype "passive"))
    )
    (net (code "77") (name "unconnected-(LINE_SISTEM-Pad5)") (class "Default")
      (node (ref "LINE_SISTEM") (pin "5") (pinfunction "5_5") (pintype "passive"))
    )
    (net (code "78") (name "unconnected-(MAIN_POWER-3-ON-Pad3)") (class "Default")
      (node (ref "MAIN_POWER") (pin "3") (pinfunction "3-ON_3") (pintype "passive"))
    )
    (net (code "79") (name "unconnected-(SMALL_LINE-Pad5)") (class "Default")
      (node (ref "SMALL_LINE") (pin "5") (pinfunction "5_5") (pintype "passive"))
    )
    (net (code "80") (name "unconnected-(U$4-PadCS)") (class "Default")
      (node (ref "U$4") (pin "CS") (pinfunction "CS_CS") (pintype "bidirectional"))
    )
    (net (code "81") (name "unconnected-(U$4-PadENA{slash}DIAGA)") (class "Default")
      (node (ref "U$4") (pin "ENA/DIAGA") (pinfunction "ENA/DIAGA_ENA/DIAGA") (pintype "bidirectional"))
    )
    (net (code "82") (name "unconnected-(U$4-PadENB{slash}DIAGB)") (class "Default")
      (node (ref "U$4") (pin "ENB/DIAGB") (pinfunction "ENB/DIAGB_ENB/DIAGB") (pintype "bidirectional"))
    )
    (net (code "83") (name "unconnected-(U$4-PadVOUT)") (class "Default")
      (node (ref "U$4") (pin "VOUT") (pinfunction "VOUT_VOUT") (pintype "bidirectional"))
    )
    (net (code "84") (name "unconnected-(U1-ADC6-Pad19)") (class "Default")
      (node (ref "U1") (pin "19") (pinfunction "ADC6_19") (pintype "bidirectional"))
    )
    (net (code "85") (name "unconnected-(U1-ADC7-Pad22)") (class "Default")
      (node (ref "U1") (pin "22") (pinfunction "ADC7_22") (pintype "bidirectional"))
    )
    (net (code "86") (name "unconnected-(U1-AREF-Pad20)") (class "Default")
      (node (ref "U1") (pin "20") (pinfunction "AREF_20") (pintype "bidirectional"))
    )
    (net (code "87") (name "unconnected-(U1-PB0(ICP)-Pad12)") (class "Default")
      (node (ref "U1") (pin "12") (pinfunction "PB0(ICP)_12") (pintype "bidirectional"))
    )
    (net (code "88") (name "unconnected-(U1-PB1(OC1A)-Pad13)") (class "Default")
      (node (ref "U1") (pin "13") (pinfunction "PB1(OC1A)_13") (pintype "bidirectional"))
    )
    (net (code "89") (name "unconnected-(U1-PC0(ADC0)-Pad23)") (class "Default")
      (node (ref "U1") (pin "23") (pinfunction "PC0(ADC0)_23") (pintype "bidirectional"))
    )
    (net (code "90") (name "unconnected-(U1-PC1(ADC1)-Pad24)") (class "Default")
      (node (ref "U1") (pin "24") (pinfunction "PC1(ADC1)_24") (pintype "bidirectional"))
    )
    (net (code "91") (name "unconnected-(U1-PC2(ADC2)-Pad25)") (class "Default")
      (node (ref "U1") (pin "25") (pinfunction "PC2(ADC2)_25") (pintype "bidirectional"))
    )
    (net (code "92") (name "unconnected-(U1-PC3(ADC3)-Pad26)") (class "Default")
      (node (ref "U1") (pin "26") (pinfunction "PC3(ADC3)_26") (pintype "bidirectional"))
    )
    (net (code "93") (name "unconnected-(U1-PC4(ADC4{slash}SDA)-Pad27)") (class "Default")
      (node (ref "U1") (pin "27") (pinfunction "PC4(ADC4/SDA)_27") (pintype "bidirectional"))
    )
    (net (code "94") (name "unconnected-(U1-PC5(ADC5{slash}SCL)-Pad28)") (class "Default")
      (node (ref "U1") (pin "28") (pinfunction "PC5(ADC5/SCL)_28") (pintype "bidirectional"))
    )
    (net (code "95") (name "unconnected-(U1-PD2(INT0)-Pad32)") (class "Default")
      (node (ref "U1") (pin "32") (pinfunction "PD2(INT0)_32") (pintype "bidirectional"))
    )
    (net (code "96") (name "unconnected-(U1-PD3(INT1)-Pad1)") (class "Default")
      (node (ref "U1") (pin "1") (pinfunction "PD3(INT1)_1") (pintype "bidirectional"))
    )
    (net (code "97") (name "unconnected-(U1-PD4(XCK{slash}T0)-Pad2)") (class "Default")
      (node (ref "U1") (pin "2") (pinfunction "PD4(XCK/T0)_2") (pintype "bidirectional"))
    )
    (net (code "98") (name "unconnected-(U2-ADC6-Pad19)") (class "Default")
      (node (ref "U2") (pin "19") (pinfunction "ADC6_19") (pintype "bidirectional"))
    )
    (net (code "99") (name "unconnected-(U2-ADC7-Pad22)") (class "Default")
      (node (ref "U2") (pin "22") (pinfunction "ADC7_22") (pintype "bidirectional"))
    )
    (net (code "100") (name "unconnected-(U2-AREF-Pad20)") (class "Default")
      (node (ref "U2") (pin "20") (pinfunction "AREF_20") (pintype "bidirectional"))
    )
    (net (code "101") (name "unconnected-(U2-PC1(ADC1)-Pad24)") (class "Default")
      (node (ref "U2") (pin "24") (pinfunction "PC1(ADC1)_24") (pintype "bidirectional"))
    )
    (net (code "102") (name "unconnected-(U2-PC2(ADC2)-Pad25)") (class "Default")
      (node (ref "U2") (pin "25") (pinfunction "PC2(ADC2)_25") (pintype "bidirectional"))
    )
    (net (code "103") (name "unconnected-(U2-PC3(ADC3)-Pad26)") (class "Default")
      (node (ref "U2") (pin "26") (pinfunction "PC3(ADC3)_26") (pintype "bidirectional"))
    )
    (net (code "104") (name "unconnected-(ULTRA_SISTEM-Pad5)") (class "Default")
      (node (ref "ULTRA_SISTEM") (pin "5") (pinfunction "5_5") (pintype "passive"))
    )
  )
)
